# PAPx2-4.net
KiCad netlist of a schematic drawn in EAGLE
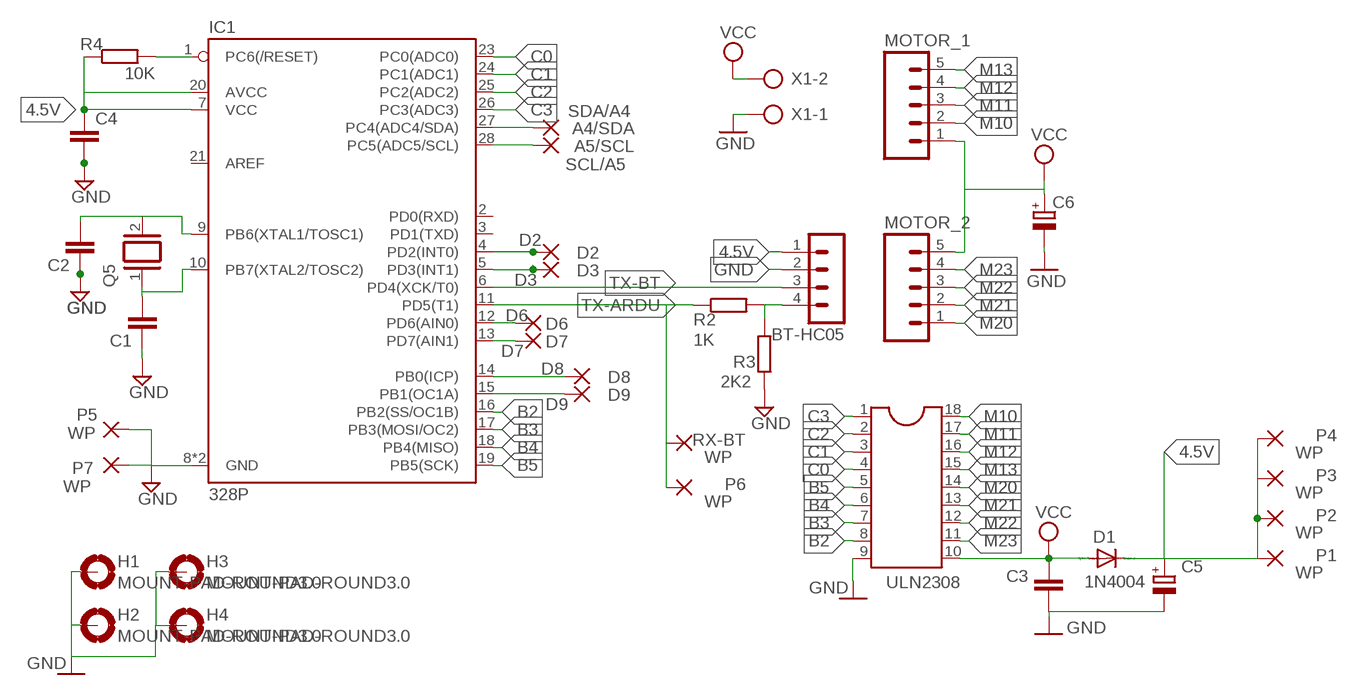
[diagram p0: schematic, sheet 1]

(export (version "E")
  (design (tool "Eeschema 10.0.6"))
  (components
    (comp (ref "BT-HC05")
      (value "MA04-1")
      (footprint "eagle-import:MA04-1")
      (libsource (lib "eagle-import") (part "MA04-1"))
    )
    (comp (ref "C1")
      (value "C-EU025-025X050")
      (footprint "eagle-import:C025-025X050")
      (libsource (lib "eagle-import") (part "C-EU025-025X050"))
    )
    (comp (ref "C2")
      (value "C-EU025-025X050")
      (footprint "eagle-import:C025-025X050")
      (libsource (lib "eagle-import") (part "C-EU025-025X050"))
    )
    (comp (ref "C3")
      (value "C-EU050-025X075")
      (footprint "eagle-import:C050-025X075")
      (libsource (lib "eagle-import") (part "C-EU050-025X075"))
    )
    (comp (ref "C4")
      (value "C-EU050-025X075")
      (footprint "eagle-import:C050-025X075")
      (libsource (lib "eagle-import") (part "C-EU050-025X075"))
    )
    (comp (ref "C5")
      (value "CPOL-EUE2.5-5")
      (footprint "eagle-import:E2,5-5")
      (libsource (lib "eagle-import") (part "CPOL-EUE2.5-5"))
    )
    (comp (ref "C6")
      (value "CPOL-EUE2.5-5")
      (footprint "eagle-import:E2,5-5")
      (libsource (lib "eagle-import") (part "CPOL-EUE2.5-5"))
    )
    (comp (ref "D1")
      (value "1N4004")
      (footprint "eagle-import:DO41-10")
      (libsource (lib "eagle-import") (part "1N4004"))
    )
    (comp (ref "D2")
      (value "D2")
      (footprint "eagle-import:1,6_0,8")
      (libsource (lib "eagle-import") (part "WIREPAD1,6/0,8"))
    )
    (comp (ref "D3")
      (value "D3")
      (footprint "eagle-import:1,6_0,8")
      (libsource (lib "eagle-import") (part "WIREPAD1,6/0,8"))
    )
    (comp (ref "D6")
      (value "D6")
      (footprint "eagle-import:1,6_0,8")
      (libsource (lib "eagle-import") (part "WIREPAD1,6/0,8"))
    )
    (comp (ref "D7")
      (value "D7")
      (footprint "eagle-import:1,6_0,8")
      (libsource (lib "eagle-import") (part "WIREPAD1,6/0,8"))
    )
    (comp (ref "D8")
      (value "D8")
      (footprint "eagle-import:1,6_0,8")
      (libsource (lib "eagle-import") (part "WIREPAD1,6/0,8"))
    )
    (comp (ref "D9")
      (value "D9")
      (footprint "eagle-import:1,6_0,8")
      (libsource (lib "eagle-import") (part "WIREPAD1,6/0,8"))
    )
    (comp (ref "H1")
      (value "MOUNT-PAD-ROUND3.0")
      (footprint "eagle-import:3,0-PAD")
      (libsource (lib "eagle-import") (part "MOUNT-PAD-ROUND3.0"))
    )
    (comp (ref "H2")
      (value "MOUNT-PAD-ROUND3.0")
      (footprint "eagle-import:3,0-PAD")
      (libsource (lib "eagle-import") (part "MOUNT-PAD-ROUND3.0"))
    )
    (comp (ref "H3")
      (value "MOUNT-PAD-ROUND3.0")
      (footprint "eagle-import:3,0-PAD")
      (libsource (lib "eagle-import") (part "MOUNT-PAD-ROUND3.0"))
    )
    (comp (ref "H4")
      (value "MOUNT-PAD-ROUND3.0")
      (footprint "eagle-import:3,0-PAD")
      (libsource (lib "eagle-import") (part "MOUNT-PAD-ROUND3.0"))
    )
    (comp (ref "IC1")
      (value "328P")
      (footprint "eagle-import:DIP28")
      (libsource (lib "eagle-import") (part "ATMEGA328P"))
    )
    (comp (ref "MOTOR_1")
      (value "M05")
      (footprint "eagle-import:05P")
      (libsource (lib "eagle-import") (part "M05"))
    )
    (comp (ref "MOTOR_2")
      (value "M05")
      (footprint "eagle-import:05P")
      (libsource (lib "eagle-import") (part "M05"))
    )
    (comp (ref "P1")
      (value "WP")
      (footprint "eagle-import:1,6_0,8")
      (libsource (lib "eagle-import") (part "WIREPAD1,6/0,8"))
    )
    (comp (ref "P2")
      (value "WP")
      (footprint "eagle-import:1,6_0,8")
      (libsource (lib "eagle-import") (part "WIREPAD1,6/0,8"))
    )
    (comp (ref "P3")
      (value "WP")
      (footprint "eagle-import:1,6_0,8")
      (libsource (lib "eagle-import") (part "WIREPAD1,6/0,8"))
    )
    (comp (ref "P4")
      (value "WP")
      (footprint "eagle-import:1,6_0,8")
      (libsource (lib "eagle-import") (part "WIREPAD1,6/0,8"))
    )
    (comp (ref "P5")
      (value "WP")
      (footprint "eagle-import:1,6_0,8")
      (libsource (lib "eagle-import") (part "WIREPAD1,6/0,8"))
    )
    (comp (ref "P6")
      (value "WP")
      (footprint "eagle-import:1,6_0,8")
      (libsource (lib "eagle-import") (part "WIREPAD1,6/0,8"))
    )
    (comp (ref "P7")
      (value "WP")
      (footprint "eagle-import:1,6_0,8")
      (libsource (lib "eagle-import") (part "WIREPAD1,6/0,8"))
    )
    (comp (ref "Q5")
      (value "XTAL/S")
      (footprint "eagle-import:QS")
      (libsource (lib "eagle-import") (part "XTAL/S"))
    )
    (comp (ref "R2")
      (value "1K")
      (footprint "eagle-import:0204_7")
      (libsource (lib "eagle-import") (part "R-EU_0204/7"))
    )
    (comp (ref "R3")
      (value "2K2")
      (footprint "eagle-import:0204_7")
      (libsource (lib "eagle-import") (part "R-EU_0204/7"))
    )
    (comp (ref "R4")
      (value "10K")
      (footprint "eagle-import:0204_7")
      (libsource (lib "eagle-import") (part "R-EU_0204/7"))
    )
    (comp (ref "RX-BT")
      (value "WP")
      (footprint "eagle-import:1,6_0,8")
      (libsource (lib "eagle-import") (part "WIREPAD1,6/0,8"))
    )
    (comp (ref "SCL/A5")
      (value "A5/SCL")
      (footprint "eagle-import:1,6_0,8")
      (libsource (lib "eagle-import") (part "WIREPAD1,6/0,8"))
    )
    (comp (ref "SDA/A4")
      (value "A4/SDA")
      (footprint "eagle-import:1,6_0,8")
      (libsource (lib "eagle-import") (part "WIREPAD1,6/0,8"))
    )
    (comp (ref "ULN2308")
      (value "DIL18")
      (footprint "eagle-import:DIL18")
      (libsource (lib "eagle-import") (part "DIL18"))
    )
    (comp (ref "X1")
      (value "AK500/2")
      (footprint "eagle-import:AK500_2")
      (libsource (lib "eagle-import") (part "AK500/2"))
    )
  )
  (nets
    (net (code "1") (name "4.5V") (class "Default")
      (node (ref "BT-HC05") (pin "1") (pinfunction "1_1") (pintype "passive"))
      (node (ref "C4") (pin "1") (pinfunction "1_1") (pintype "passive"))
      (node (ref "C5") (pin "+") (pinfunction "+_+") (pintype "passive"))
      (node (ref "D1") (pin "C") (pinfunction "C_C") (pintype "passive"))
      (node (ref "IC1") (pin "20") (pinfunction "AVCC_20") (pintype "bidirectional"))
      (node (ref "IC1") (pin "7") (pinfunction "VCC_7") (pintype "bidirectional"))
      (node (ref "P1") (pin "1") (pinfunction "P_1") (pintype "passive"))
      (node (ref "P2") (pin "1") (pinfunction "P_1") (pintype "passive"))
      (node (ref "P3") (pin "1") (pinfunction "P_1") (pintype "passive"))
      (node (ref "P4") (pin "1") (pinfunction "P_1") (pintype "passive"))
      (node (ref "R4") (pin "1") (pinfunction "1_1") (pintype "passive"))
    )
    (net (code "2") (name "B2") (class "Default")
      (node (ref "IC1") (pin "16") (pinfunction "PB2(SS/OC1B)_16") (pintype "bidirectional"))
      (node (ref "ULN2308") (pin "8") (pinfunction "8_8") (pintype "passive"))
    )
    (net (code "3") (name "B3") (class "Default")
      (node (ref "IC1") (pin "17") (pinfunction "PB3(MOSI/OC2)_17") (pintype "bidirectional"))
      (node (ref "ULN2308") (pin "7") (pinfunction "7_7") (pintype "passive"))
    )
    (net (code "4") (name "B4") (class "Default")
      (node (ref "IC1") (pin "18") (pinfunction "PB4(MISO)_18") (pintype "bidirectional"))
      (node (ref "ULN2308") (pin "6") (pinfunction "6_6") (pintype "passive"))
    )
    (net (code "5") (name "B5") (class "Default")
      (node (ref "IC1") (pin "19") (pinfunction "PB5(SCK)_19") (pintype "bidirectional"))
      (node (ref "ULN2308") (pin "5") (pinfunction "5_5") (pintype "passive"))
    )
    (net (code "6") (name "C0") (class "Default")
      (node (ref "IC1") (pin "23") (pinfunction "PC0(ADC0)_23") (pintype "bidirectional"))
      (node (ref "ULN2308") (pin "4") (pinfunction "4_4") (pintype "passive"))
    )
    (net (code "7") (name "C1") (class "Default")
      (node (ref "IC1") (pin "24") (pinfunction "PC1(ADC1)_24") (pintype "bidirectional"))
      (node (ref "ULN2308") (pin "3") (pinfunction "3_3") (pintype "passive"))
    )
    (net (code "8") (name "C2") (class "Default")
      (node (ref "IC1") (pin "25") (pinfunction "PC2(ADC2)_25") (pintype "bidirectional"))
      (node (ref "ULN2308") (pin "2") (pinfunction "2_2") (pintype "passive"))
    )
    (net (code "9") (name "C3") (class "Default")
      (node (ref "IC1") (pin "26") (pinfunction "PC3(ADC3)_26") (pintype "bidirectional"))
      (node (ref "ULN2308") (pin "1") (pinfunction "1_1") (pintype "passive"))
    )
    (net (code "10") (name "GND") (class "Default")
      (node (ref "BT-HC05") (pin "2") (pinfunction "2_2") (pintype "passive"))
      (node (ref "C1") (pin "1") (pinfunction "1_1") (pintype "passive"))
      (node (ref "C2") (pin "1") (pinfunction "1_1") (pintype "passive"))
      (node (ref "C3") (pin "2") (pinfunction "2_2") (pintype "passive"))
      (node (ref "C4") (pin "2") (pinfunction "2_2") (pintype "passive"))
      (node (ref "C5") (pin "-") (pinfunction "-_-") (pintype "passive"))
      (node (ref "C6") (pin "-") (pinfunction "-_-") (pintype "passive"))
      (node (ref "H1") (pin "B3,0") (pinfunction "MOUNT_B3,0") (pintype "passive"))
      (node (ref "H2") (pin "B3,0") (pinfunction "MOUNT_B3,0") (pintype "passive"))
      (node (ref "H3") (pin "B3,0") (pinfunction "MOUNT_B3,0") (pintype "passive"))
      (node (ref "H4") (pin "B3,0") (pinfunction "MOUNT_B3,0") (pintype "passive"))
      (node (ref "IC1") (pin "22") (pinfunction "GND_22") (pintype "bidirectional"))
      (node (ref "IC1") (pin "8") (pinfunction "GND_8") (pintype "bidirectional"))
      (node (ref "P5") (pin "1") (pinfunction "P_1") (pintype "passive"))
      (node (ref "P7") (pin "1") (pinfunction "P_1") (pintype "passive"))
      (node (ref "R3") (pin "1") (pinfunction "1_1") (pintype "passive"))
      (node (ref "ULN2308") (pin "9") (pinfunction "9_9") (pintype "passive"))
      (node (ref "X1") (pin "1") (pinfunction "KL_1") (pintype "passive"))
    )
    (net (code "11") (name "M10") (class "Default")
      (node (ref "MOTOR_1") (pin "2") (pinfunction "2_2") (pintype "passive"))
      (node (ref "ULN2308") (pin "18") (pinfunction "18_18") (pintype "passive"))
    )
    (net (code "12") (name "M11") (class "Default")
      (node (ref "MOTOR_1") (pin "3") (pinfunction "3_3") (pintype "passive"))
      (node (ref "ULN2308") (pin "17") (pinfunction "17_17") (pintype "passive"))
    )
    (net (code "13") (name "M12") (class "Default")
      (node (ref "MOTOR_1") (pin "4") (pinfunction "4_4") (pintype "passive"))
      (node (ref "ULN2308") (pin "16") (pinfunction "16_16") (pintype "passive"))
    )
    (net (code "14") (name "M13") (class "Default")
      (node (ref "MOTOR_1") (pin "5") (pinfunction "5_5") (pintype "passive"))
      (node (ref "ULN2308") (pin "15") (pinfunction "15_15") (pintype "passive"))
    )
    (net (code "15") (name "M20") (class "Default")
      (node (ref "MOTOR_2") (pin "1") (pinfunction "1_1") (pintype "passive"))
      (node (ref "ULN2308") (pin "14") (pinfunction "14_14") (pintype "passive"))
    )
    (net (code "16") (name "M21") (class "Default")
      (node (ref "MOTOR_2") (pin "2") (pinfunction "2_2") (pintype "passive"))
      (node (ref "ULN2308") (pin "13") (pinfunction "13_13") (pintype "passive"))
    )
    (net (code "17") (name "M22") (class "Default")
      (node (ref "MOTOR_2") (pin "3") (pinfunction "3_3") (pintype "passive"))
      (node (ref "ULN2308") (pin "12") (pinfunction "12_12") (pintype "passive"))
    )
    (net (code "18") (name "M23") (class "Default")
      (node (ref "MOTOR_2") (pin "4") (pinfunction "4_4") (pintype "passive"))
      (node (ref "ULN2308") (pin "11") (pinfunction "11_11") (pintype "passive"))
    )
    (net (code "19") (name "Net-(BT-HC05-Pad4)") (class "Default")
      (node (ref "BT-HC05") (pin "4") (pinfunction "4_4") (pintype "passive"))
      (node (ref "R2") (pin "2") (pinfunction "2_2") (pintype "passive"))
      (node (ref "R3") (pin "2") (pinfunction "2_2") (pintype "passive"))
    )
    (net (code "20") (name "Net-(D2-P)") (class "Default")
      (node (ref "D2") (pin "1") (pinfunction "P_1") (pintype "passive"))
      (node (ref "IC1") (pin "4") (pinfunction "PD2(INT0)_4") (pintype "bidirectional"))
    )
    (net (code "21") (name "Net-(D3-P)") (class "Default")
      (node (ref "D3") (pin "1") (pinfunction "P_1") (pintype "passive"))
      (node (ref "IC1") (pin "5") (pinfunction "PD3(INT1)_5") (pintype "bidirectional"))
    )
    (net (code "22") (name "Net-(D6-P)") (class "Default")
      (node (ref "D6") (pin "1") (pinfunction "P_1") (pintype "passive"))
      (node (ref "IC1") (pin "12") (pinfunction "PD6(AIN0)_12") (pintype "bidirectional"))
    )
    (net (code "23") (name "Net-(D7-P)") (class "Default")
      (node (ref "D7") (pin "1") (pinfunction "P_1") (pintype "passive"))
      (node (ref "IC1") (pin "13") (pinfunction "PD7(AIN1)_13") (pintype "bidirectional"))
    )
    (net (code "24") (name "Net-(D8-P)") (class "Default")
      (node (ref "D8") (pin "1") (pinfunction "P_1") (pintype "passive"))
      (node (ref "IC1") (pin "14") (pinfunction "PB0(ICP)_14") (pintype "bidirectional"))
    )
    (net (code "25") (name "Net-(D9-P)") (class "Default")
      (node (ref "D9") (pin "1") (pinfunction "P_1") (pintype "passive"))
      (node (ref "IC1") (pin "15") (pinfunction "PB1(OC1A)_15") (pintype "bidirectional"))
    )
    (net (code "26") (name "Net-(IC1-PB6(XTAL1{slash}TOSC1))") (class "Default")
      (node (ref "C2") (pin "2") (pinfunction "2_2") (pintype "passive"))
      (node (ref "IC1") (pin "9") (pinfunction "PB6(XTAL1/TOSC1)_9") (pintype "bidirectional"))
      (node (ref "Q5") (pin "2") (pinfunction "2_2") (pintype "passive"))
    )
    (net (code "27") (name "Net-(IC1-PB7(XTAL2{slash}TOSC2))") (class "Default")
      (node (ref "C1") (pin "2") (pinfunction "2_2") (pintype "passive"))
      (node (ref "IC1") (pin "10") (pinfunction "PB7(XTAL2/TOSC2)_10") (pintype "bidirectional"))
      (node (ref "Q5") (pin "1") (pinfunction "1_1") (pintype "passive"))
    )
    (net (code "28") (name "Net-(IC1-PC4(ADC4{slash}SDA))") (class "Default")
      (node (ref "IC1") (pin "27") (pinfunction "PC4(ADC4/SDA)_27") (pintype "bidirectional"))
      (node (ref "SDA/A4") (pin "1") (pinfunction "P_1") (pintype "passive"))
    )
    (net (code "29") (name "Net-(IC1-PC5(ADC5{slash}SCL))") (class "Default")
      (node (ref "IC1") (pin "28") (pinfunction "PC5(ADC5/SCL)_28") (pintype "bidirectional"))
      (node (ref "SCL/A5") (pin "1") (pinfunction "P_1") (pintype "passive"))
    )
    (net (code "30") (name "Net-(IC1-PC6({slash}RESET))") (class "Default")
      (node (ref "IC1") (pin "1") (pinfunction "PC6(/RESET)_1") (pintype "bidirectional"))
      (node (ref "R4") (pin "2") (pinfunction "2_2") (pintype "passive"))
    )
    (net (code "31") (name "TX-ARDU") (class "Default")
      (node (ref "IC1") (pin "11") (pinfunction "PD5(T1)_11") (pintype "bidirectional"))
      (node (ref "P6") (pin "1") (pinfunction "P_1") (pintype "passive"))
      (node (ref "R2") (pin "1") (pinfunction "1_1") (pintype "passive"))
      (node (ref "RX-BT") (pin "1") (pinfunction "P_1") (pintype "passive"))
    )
    (net (code "32") (name "TX-BT") (class "Default")
      (node (ref "BT-HC05") (pin "3") (pinfunction "3_3") (pintype "passive"))
      (node (ref "IC1") (pin "6") (pinfunction "PD4(XCK/T0)_6") (pintype "bidirectional"))
    )
    (net (code "33") (name "VCC") (class "Default")
      (node (ref "C3") (pin "1") (pinfunction "1_1") (pintype "passive"))
      (node (ref "C6") (pin "+") (pinfunction "+_+") (pintype "passive"))
      (node (ref "D1") (pin "A") (pinfunction "A_A") (pintype "passive"))
      (node (ref "MOTOR_1") (pin "1") (pinfunction "1_1") (pintype "passive"))
      (node (ref "MOTOR_2") (pin "5") (pinfunction "5_5") (pintype "passive"))
      (node (ref "ULN2308") (pin "10") (pinfunction "10_10") (pintype "passive"))
      (node (ref "X1") (pin "2") (pinfunction "KL_2") (pintype "passive"))
    )
    (net (code "34") (name "unconnected-(IC1-AREF-Pad21)") (class "Default")
      (node (ref "IC1") (pin "21") (pinfunction "AREF_21") (pintype "bidirectional"))
    )
    (net (code "35") (name "unconnected-(IC1-PD0(RXD)-Pad2)") (class "Default")
      (node (ref "IC1") (pin "2") (pinfunction "PD0(RXD)_2") (pintype "bidirectional"))
    )
    (net (code "36") (name "unconnected-(IC1-PD1(TXD)-Pad3)") (class "Default")
      (node (ref "IC1") (pin "3") (pinfunction "PD1(TXD)_3") (pintype "bidirectional"))
    )
  )
)
